# bms_interface.net
KiCad netlist of a schematic drawn in Altium Designer
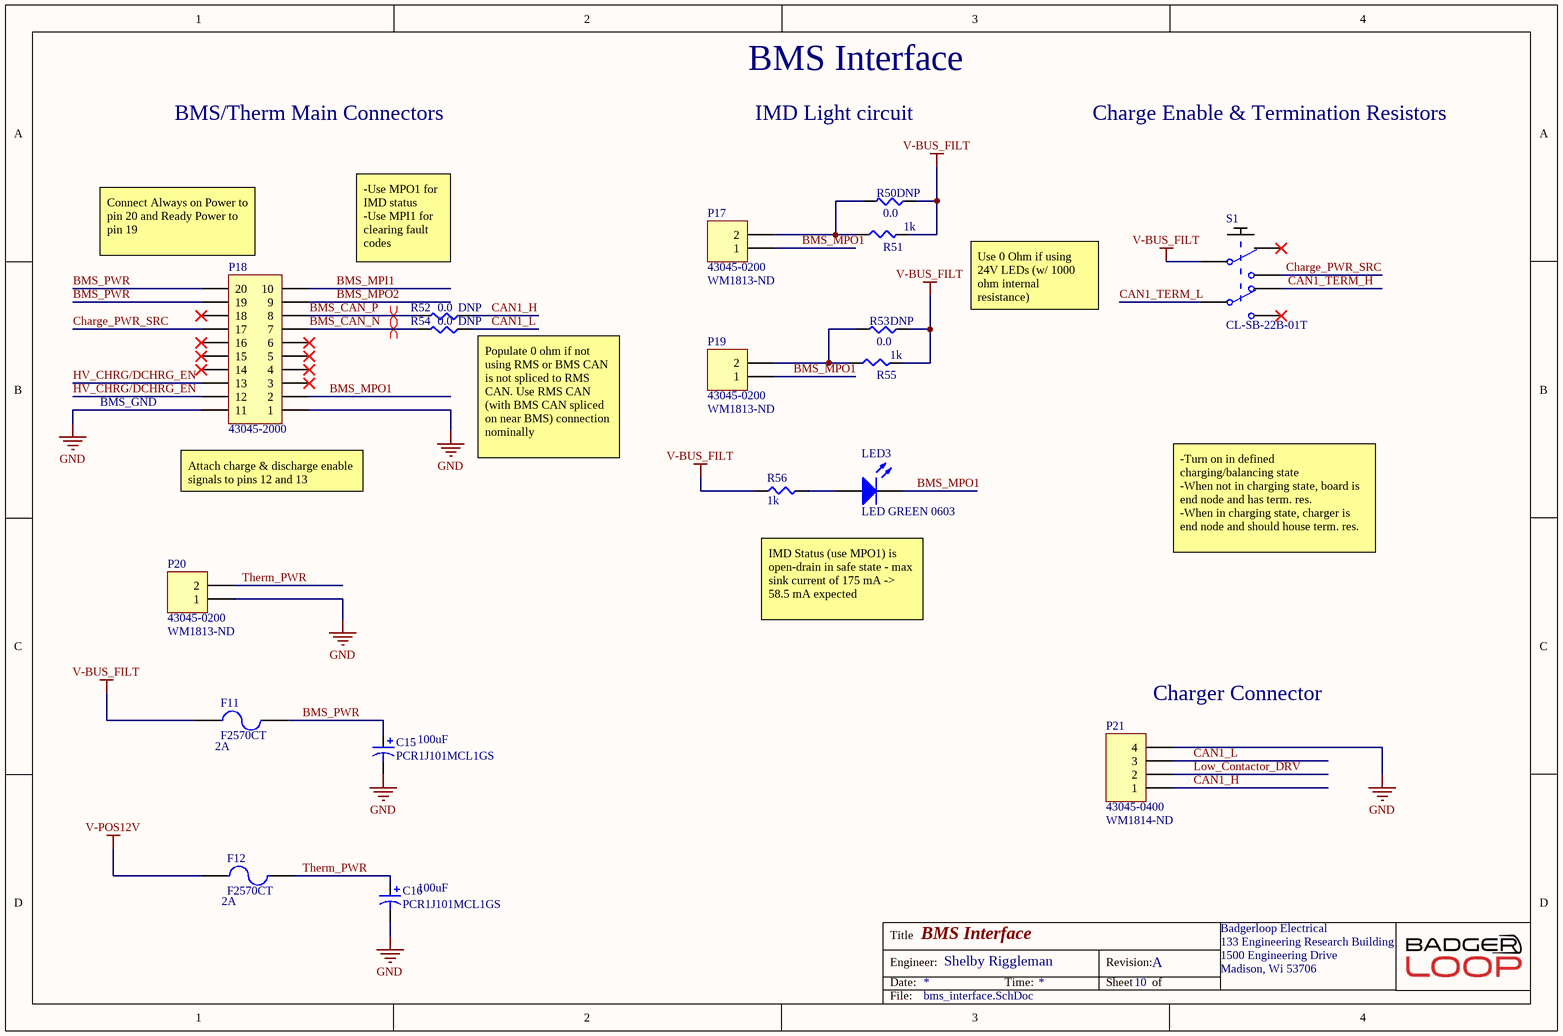
[diagram p0: bms_interface.SchDoc]

(export (version "E")
  (design (tool "Eeschema 10.0.6"))
  (components
    (comp (ref "C15")
      (value "PCR1J101MCL1GS")
      (footprint "CAPAE110103X126M")
      (description "CAP ALUM POLY 100UF 20% 63V SMD")
      (fields
        (field (name "MANUFACTURER") "Nichicon")
        (field (name "CAPACITANCE") "100uF")
        (field (name "TOLERANCE") "20%")
      )
      (libsource (lib "capacitors") (part "PCR1J101MCL1GS"))
    )
    (comp (ref "C16")
      (value "PCR1J101MCL1GS")
      (footprint "CAPAE110103X126M")
      (description "CAP ALUM POLY 100UF 20% 63V SMD")
      (fields
        (field (name "MANUFACTURER") "Nichicon")
        (field (name "CAPACITANCE") "100uF")
        (field (name "TOLERANCE") "20%")
      )
      (libsource (lib "capacitors") (part "PCR1J101MCL1GS"))
    )
    (comp (ref "F11")
      (value "F2570CT")
      (footprint "SMD-1206-RES")
      (description "FUSE BOARD MNT 2A 63VAC/VDC 1206")
      (fields
        (field (name "MANUFACTURER") "Littelfuse")
        (field (name "CURRENT RATING") "2A")
        (field (name "MANUFACTURER PART NUMBER") "0468002.NR")
      )
      (libsource (lib "misc") (part "F2570CT"))
    )
    (comp (ref "F12")
      (value "F2570CT")
      (footprint "SMD-1206-RES")
      (description "FUSE BOARD MNT 2A 63VAC/VDC 1206")
      (fields
        (field (name "MANUFACTURER") "Littelfuse")
        (field (name "CURRENT RATING") "2A")
        (field (name "MANUFACTURER PART NUMBER") "0468002.NR")
      )
      (libsource (lib "misc") (part "F2570CT"))
    )
    (comp (ref "LED3")
      (value "LED GREEN 0603")
      (footprint "LED 0603 GREEN")
      (fields (field (name "MANUFACTURER") "Lite-On Inc."))
      (libsource (lib "misc") (part "LED GREEN 0603"))
    )
    (comp (ref "P17")
      (value "43045-0200")
      (footprint "430450200")
      (description "CONN HEADER R/A 2POS")
      (fields (field (name "MANUFACTURER") "Molex") (field (name "SUPPLIER PART NUMBER 1") "WM1813-ND"))
      (libsource (lib "connector") (part "43045-0200"))
    )
    (comp (ref "P18")
      (value "43045-2000")
      (footprint "430452000")
      (description "HEADER, RIGHT ANGLE, 20WAY")
      (fields (field (name "MANUFACTURER") "Molex"))
      (libsource (lib "connector") (part "43045-2000"))
    )
    (comp (ref "P19")
      (value "43045-0200")
      (footprint "430450200")
      (description "CONN HEADER R/A 2POS")
      (fields (field (name "MANUFACTURER") "Molex") (field (name "SUPPLIER PART NUMBER 1") "WM1813-ND"))
      (libsource (lib "connector") (part "43045-0200"))
    )
    (comp (ref "P20")
      (value "43045-0200")
      (footprint "430450200")
      (description "CONN HEADER R/A 2POS")
      (fields (field (name "MANUFACTURER") "Molex") (field (name "SUPPLIER PART NUMBER 1") "WM1813-ND"))
      (libsource (lib "connector") (part "43045-0200"))
    )
    (comp (ref "P21")
      (value "43045-0400")
      (footprint "430450400")
      (description "Male connector dual row 90° 3 mm Pole no. 2x2 Micro-Fit, 43045-0400, Molex")
      (fields (field (name "MANUFACTURER") "Molex") (field (name "SUPPLIER PART NUMBER 1") "WM1814-ND"))
      (libsource (lib "connector") (part "43045-0400"))
    )
    (comp (ref "R50")
      (value "0.0")
      (footprint "SMD-0805-RES")
      (description "RES SMD 0.0 OHM JUMPER 1/8W 0805")
      (fields
        (field (name "PART NUMBER") "ERJ-6GEY0R00V")
        (field (name "DIGI-KEY PART NUMBER") "P0.0ACT-ND")
        (field (name "DNP") "DNP")
      )
      (libsource (lib "resistors") (part "ERJ-6GEY0R00V"))
    )
    (comp (ref "R51")
      (value "1k")
      (footprint "SMD-0805-RES")
      (description "RES SMD 1K OHM 5% 1/2W 0805")
      (fields
        (field (name "PART NUMBER") "ERJ-P06J102V")
        (field (name "DIGI-KEY PART NUMBER") "P1.0KADCT-ND")
      )
      (libsource (lib "resistors") (part "ERJ-P06J102V"))
    )
    (comp (ref "R52")
      (value "0.0")
      (footprint "SMD-0805-RES")
      (description "RES SMD 0.0 OHM JUMPER 1/8W 0805")
      (fields
        (field (name "PART NUMBER") "ERJ-6GEY0R00V")
        (field (name "DIGI-KEY PART NUMBER") "P0.0ACT-ND")
        (field (name "DNP") "DNP")
      )
      (libsource (lib "resistors") (part "ERJ-6GEY0R00V"))
    )
    (comp (ref "R53")
      (value "0.0")
      (footprint "SMD-0805-RES")
      (description "RES SMD 0.0 OHM JUMPER 1/8W 0805")
      (fields
        (field (name "PART NUMBER") "ERJ-6GEY0R00V")
        (field (name "DIGI-KEY PART NUMBER") "P0.0ACT-ND")
        (field (name "DNP") "DNP")
      )
      (libsource (lib "resistors") (part "ERJ-6GEY0R00V"))
    )
    (comp (ref "R54")
      (value "0.0")
      (footprint "SMD-0805-RES")
      (description "RES SMD 0.0 OHM JUMPER 1/8W 0805")
      (fields
        (field (name "PART NUMBER") "ERJ-6GEY0R00V")
        (field (name "DIGI-KEY PART NUMBER") "P0.0ACT-ND")
        (field (name "DNP") "DNP")
      )
      (libsource (lib "resistors") (part "ERJ-6GEY0R00V"))
    )
    (comp (ref "R55")
      (value "1k")
      (footprint "SMD-0805-RES")
      (description "RES SMD 1K OHM 5% 1/2W 0805")
      (fields
        (field (name "PART NUMBER") "ERJ-P06J102V")
        (field (name "DIGI-KEY PART NUMBER") "P1.0KADCT-ND")
      )
      (libsource (lib "resistors") (part "ERJ-P06J102V"))
    )
    (comp (ref "R56")
      (value "1k")
      (footprint "SMD-0805-RES")
      (description "RES SMD 1K OHM 5% 1/2W 0805")
      (fields
        (field (name "PART NUMBER") "ERJ-P06J102V")
        (field (name "DIGI-KEY PART NUMBER") "P1.0KADCT-ND")
      )
      (libsource (lib "resistors") (part "ERJ-P06J102V"))
    )
    (comp (ref "S1")
      (value "CL-SB-22B-01T")
      (footprint "SOP250P500X350-6N")
      (description "SWITCH SLIDE DPDT 200MA 12V")
      (fields (field (name "MANUFACTURER") "Nidec Copal"))
      (libsource (lib "misc") (part "CL-SB-22B-01T"))
    )
  )
  (nets
    (net (code "1") (name "/BMS_CAN_N") (class "Default")
      (node (ref "P18") (pin "7") (pinfunction "7_7") (pintype "passive"))
      (node (ref "R54") (pin "2") (pinfunction "2_2") (pintype "passive"))
    )
    (net (code "2") (name "/BMS_CAN_P") (class "Default")
      (node (ref "P18") (pin "8") (pinfunction "8_8") (pintype "passive"))
      (node (ref "R52") (pin "2") (pinfunction "2_2") (pintype "passive"))
    )
    (net (code "3") (name "/BMS_MPI1") (class "Default")
      (node (ref "P18") (pin "10") (pinfunction "10_10") (pintype "passive"))
    )
    (net (code "4") (name "/BMS_MPO1") (class "Default")
      (node (ref "LED3") (pin "2") (pinfunction "K_2") (pintype "passive"))
      (node (ref "P17") (pin "1") (pinfunction "1_1") (pintype "passive"))
      (node (ref "P18") (pin "2") (pinfunction "2_2") (pintype "passive"))
      (node (ref "P19") (pin "1") (pinfunction "1_1") (pintype "passive"))
    )
    (net (code "5") (name "/BMS_MPO2") (class "Default")
      (node (ref "P18") (pin "9") (pinfunction "9_9") (pintype "passive"))
    )
    (net (code "6") (name "/BMS_PWR") (class "Default")
      (node (ref "C15") (pin "1") (pinfunction "1_1") (pintype "passive"))
      (node (ref "F11") (pin "2") (pinfunction "2_2") (pintype "passive"))
      (node (ref "P18") (pin "19") (pinfunction "19_19") (pintype "passive"))
      (node (ref "P18") (pin "20") (pinfunction "20_20") (pintype "passive"))
    )
    (net (code "7") (name "/CAN1_H") (class "Default")
      (node (ref "P21") (pin "1") (pinfunction "1_1") (pintype "passive"))
      (node (ref "R52") (pin "1") (pinfunction "1_1") (pintype "passive"))
    )
    (net (code "8") (name "/CAN1_L") (class "Default")
      (node (ref "P21") (pin "3") (pinfunction "3_3") (pintype "passive"))
      (node (ref "R54") (pin "1") (pinfunction "1_1") (pintype "passive"))
    )
    (net (code "9") (name "/CAN1_TERM_H") (class "Default")
      (node (ref "S1") (pin "4") (pinfunction "4_4") (pintype "passive"))
    )
    (net (code "10") (name "/CAN1_TERM_L") (class "Default")
      (node (ref "S1") (pin "5") (pinfunction "5_5") (pintype "passive"))
    )
    (net (code "11") (name "/Charge_PWR_SRC") (class "Default")
      (node (ref "P18") (pin "17") (pinfunction "17_17") (pintype "passive"))
      (node (ref "S1") (pin "3") (pinfunction "3_3") (pintype "passive"))
    )
    (net (code "12") (name "/HV_CHRG{slash}DCHRG_EN") (class "Default")
      (node (ref "P18") (pin "12") (pinfunction "12_12") (pintype "passive"))
      (node (ref "P18") (pin "13") (pinfunction "13_13") (pintype "passive"))
    )
    (net (code "13") (name "/Low_Contactor_DRV") (class "Default")
      (node (ref "P21") (pin "2") (pinfunction "2_2") (pintype "passive"))
    )
    (net (code "14") (name "/Therm_PWR") (class "Default")
      (node (ref "C16") (pin "1") (pinfunction "1_1") (pintype "passive"))
      (node (ref "F12") (pin "2") (pinfunction "2_2") (pintype "passive"))
      (node (ref "P20") (pin "2") (pinfunction "2_2") (pintype "passive"))
    )
    (net (code "15") (name "GND") (class "Default")
      (node (ref "C15") (pin "2") (pinfunction "2_2") (pintype "passive"))
      (node (ref "C16") (pin "2") (pinfunction "2_2") (pintype "passive"))
      (node (ref "P18") (pin "1") (pinfunction "1_1") (pintype "passive"))
      (node (ref "P18") (pin "11") (pinfunction "11_11") (pintype "passive"))
      (node (ref "P20") (pin "1") (pinfunction "1_1") (pintype "passive"))
      (node (ref "P21") (pin "4") (pinfunction "4_4") (pintype "passive"))
    )
    (net (code "16") (name "Net-(LED3-A)") (class "Default")
      (node (ref "LED3") (pin "1") (pinfunction "A_1") (pintype "passive"))
      (node (ref "R56") (pin "2") (pinfunction "2_2") (pintype "passive"))
    )
    (net (code "17") (name "Net-(P17-Pad2)") (class "Default")
      (node (ref "P17") (pin "2") (pinfunction "2_2") (pintype "passive"))
      (node (ref "R50") (pin "2") (pinfunction "2_2") (pintype "passive"))
      (node (ref "R51") (pin "1") (pinfunction "1_1") (pintype "passive"))
    )
    (net (code "18") (name "Net-(P19-Pad2)") (class "Default")
      (node (ref "P19") (pin "2") (pinfunction "2_2") (pintype "passive"))
      (node (ref "R53") (pin "2") (pinfunction "2_2") (pintype "passive"))
      (node (ref "R55") (pin "1") (pinfunction "1_1") (pintype "passive"))
    )
    (net (code "19") (name "V-BUS_FILT") (class "Default")
      (node (ref "F11") (pin "1") (pinfunction "1_1") (pintype "passive"))
      (node (ref "R50") (pin "1") (pinfunction "1_1") (pintype "passive"))
      (node (ref "R51") (pin "2") (pinfunction "2_2") (pintype "passive"))
      (node (ref "R53") (pin "1") (pinfunction "1_1") (pintype "passive"))
      (node (ref "R55") (pin "2") (pinfunction "2_2") (pintype "passive"))
      (node (ref "R56") (pin "1") (pinfunction "1_1") (pintype "passive"))
      (node (ref "S1") (pin "2") (pinfunction "2_2") (pintype "passive"))
    )
    (net (code "20") (name "V-POS12V") (class "Default")
      (node (ref "F12") (pin "1") (pinfunction "1_1") (pintype "passive"))
    )
    (net (code "21") (name "unconnected-(P18-Pad3)") (class "Default")
      (node (ref "P18") (pin "3") (pinfunction "3_3") (pintype "passive+no_connect"))
    )
    (net (code "22") (name "unconnected-(P18-Pad4)") (class "Default")
      (node (ref "P18") (pin "4") (pinfunction "4_4") (pintype "passive+no_connect"))
    )
    (net (code "23") (name "unconnected-(P18-Pad5)") (class "Default")
      (node (ref "P18") (pin "5") (pinfunction "5_5") (pintype "passive+no_connect"))
    )
    (net (code "24") (name "unconnected-(P18-Pad6)") (class "Default")
      (node (ref "P18") (pin "6") (pinfunction "6_6") (pintype "passive+no_connect"))
    )
    (net (code "25") (name "unconnected-(P18-Pad14)") (class "Default")
      (node (ref "P18") (pin "14") (pinfunction "14_14") (pintype "passive+no_connect"))
    )
    (net (code "26") (name "unconnected-(P18-Pad15)") (class "Default")
      (node (ref "P18") (pin "15") (pinfunction "15_15") (pintype "passive+no_connect"))
    )
    (net (code "27") (name "unconnected-(P18-Pad16)") (class "Default")
      (node (ref "P18") (pin "16") (pinfunction "16_16") (pintype "passive+no_connect"))
    )
    (net (code "28") (name "unconnected-(P18-Pad18)") (class "Default")
      (node (ref "P18") (pin "18") (pinfunction "18_18") (pintype "passive+no_connect"))
    )
    (net (code "29") (name "unconnected-(S1-Pad1)") (class "Default")
      (node (ref "S1") (pin "1") (pinfunction "1_1") (pintype "passive+no_connect"))
    )
    (net (code "30") (name "unconnected-(S1-Pad6)") (class "Default")
      (node (ref "S1") (pin "6") (pinfunction "6_6") (pintype "passive+no_connect"))
    )
  )
)
